# usbB_isp_no_lm2940.net
KiCad netlist of a schematic drawn in EAGLE
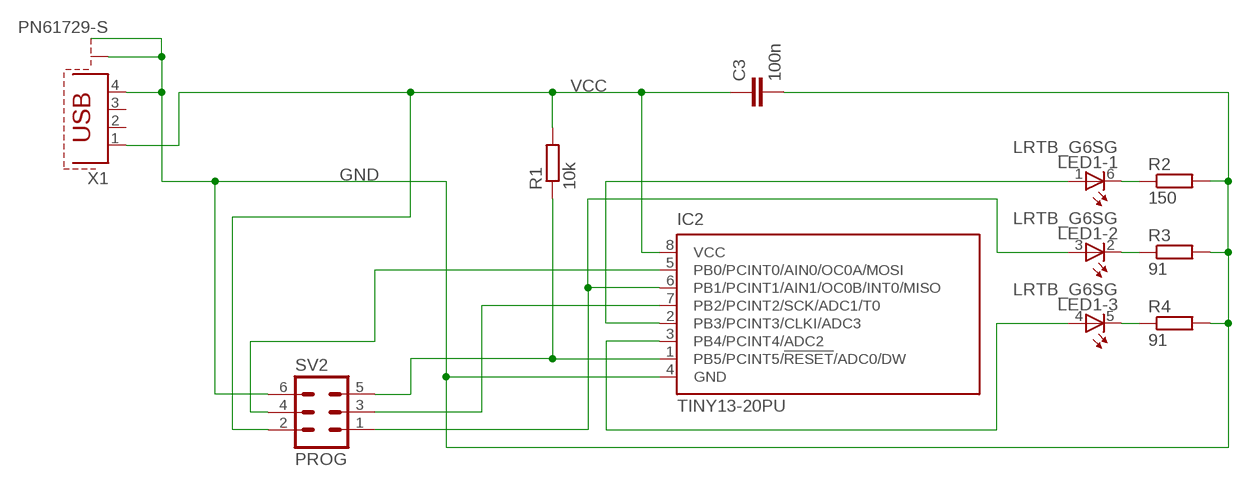
[diagram p0: schematic, sheet 1]

(export (version "E")
  (design (tool "Eeschema 10.0.6"))
  (components
    (comp (ref "C3")
      (value "100n")
      (footprint "eagle-import:C025-025X050")
      (libsource (lib "eagle-import") (part "C-EU025-025X050"))
    )
    (comp (ref "IC2")
      (value "TINY13-20PU")
      (footprint "eagle-import:DIL08")
      (fields (field (name "MPN") "ATTINY13-20PU"))
      (libsource (lib "eagle-import") (part "TINY13PU-20"))
    )
    (comp (ref "LED1")
      (value "LRTB_G6SG")
      (footprint "eagle-import:LRTB_G6SG")
      (libsource (lib "eagle-import") (part "LRTB_G6SG"))
    )
    (comp (ref "R1")
      (value "10k")
      (footprint "eagle-import:0207_10")
      (libsource (lib "eagle-import") (part "R-EU_0207/10"))
    )
    (comp (ref "R2")
      (value "150")
      (footprint "eagle-import:0207_10")
      (libsource (lib "eagle-import") (part "R-EU_0207/10"))
    )
    (comp (ref "R3")
      (value "91")
      (footprint "eagle-import:0207_10")
      (libsource (lib "eagle-import") (part "R-EU_0207/10"))
    )
    (comp (ref "R4")
      (value "91")
      (footprint "eagle-import:0207_10")
      (libsource (lib "eagle-import") (part "R-EU_0207/10"))
    )
    (comp (ref "SV2")
      (value "PROG")
      (footprint "eagle-import:ML6")
      (libsource (lib "eagle-import") (part "ML6"))
    )
    (comp (ref "X1")
      (value "PN61729-S")
      (footprint "eagle-import:PN61729-S")
      (libsource (lib "eagle-import") (part "PN61729-S"))
    )
  )
  (nets
    (net (code "1") (name "/GND") (class "Default")
      (node (ref "C3") (pin "2") (pinfunction "2_2") (pintype "passive"))
      (node (ref "IC2") (pin "4") (pinfunction "GND_4") (pintype "power_in"))
      (node (ref "R2") (pin "2") (pinfunction "2_2") (pintype "passive"))
      (node (ref "R3") (pin "2") (pinfunction "2_2") (pintype "passive"))
      (node (ref "R4") (pin "2") (pinfunction "2_2") (pintype "passive"))
      (node (ref "SV2") (pin "6") (pinfunction "6_6") (pintype "passive"))
      (node (ref "X1") (pin "4") (pinfunction "4_4") (pintype "passive"))
      (node (ref "X1") (pin "S1") (pinfunction "S1_S1") (pintype "passive"))
    )
    (net (code "2") (name "/VCC") (class "Default")
      (node (ref "C3") (pin "1") (pinfunction "1_1") (pintype "passive"))
      (node (ref "IC2") (pin "8") (pinfunction "VCC_8") (pintype "power_in"))
      (node (ref "R1") (pin "2") (pinfunction "2_2") (pintype "passive"))
      (node (ref "SV2") (pin "2") (pinfunction "2_2") (pintype "passive"))
      (node (ref "X1") (pin "1") (pinfunction "1_1") (pintype "passive"))
    )
    (net (code "3") (name "Net-(IC2-PB0{slash}PCINT0{slash}AIN0{slash}OC0A{slash}MOSI)") (class "Default")
      (node (ref "IC2") (pin "5") (pinfunction "PB0/PCINT0/AIN0/OC0A/MOSI_5") (pintype "bidirectional"))
      (node (ref "SV2") (pin "4") (pinfunction "4_4") (pintype "passive"))
    )
    (net (code "4") (name "Net-(IC2-PB1{slash}PCINT1{slash}AIN1{slash}OC0B{slash}INT0{slash}MISO)") (class "Default")
      (node (ref "IC2") (pin "6") (pinfunction "PB1/PCINT1/AIN1/OC0B/INT0/MISO_6") (pintype "bidirectional"))
      (node (ref "LED1") (pin "3") (pinfunction "A_3") (pintype "passive"))
      (node (ref "SV2") (pin "1") (pinfunction "1_1") (pintype "passive"))
    )
    (net (code "5") (name "Net-(IC2-PB2{slash}PCINT2{slash}SCK{slash}ADC1{slash}T0)") (class "Default")
      (node (ref "IC2") (pin "7") (pinfunction "PB2/PCINT2/SCK/ADC1/T0_7") (pintype "bidirectional"))
      (node (ref "SV2") (pin "3") (pinfunction "3_3") (pintype "passive"))
    )
    (net (code "6") (name "Net-(IC2-PB3{slash}PCINT3{slash}CLKI{slash}ADC3)") (class "Default")
      (node (ref "IC2") (pin "2") (pinfunction "PB3/PCINT3/CLKI/ADC3_2") (pintype "bidirectional"))
      (node (ref "LED1") (pin "1") (pinfunction "A_1") (pintype "passive"))
    )
    (net (code "7") (name "Net-(IC2-PB4{slash}PCINT4{slash}ADC2)") (class "Default")
      (node (ref "IC2") (pin "3") (pinfunction "PB4/PCINT4/ADC2_3") (pintype "bidirectional"))
      (node (ref "LED1") (pin "4") (pinfunction "A_4") (pintype "passive"))
    )
    (net (code "8") (name "Net-(IC2-PB5{slash}PCINT5{slash}~{RESET}{slash}ADC0{slash}DW)") (class "Default")
      (node (ref "IC2") (pin "1") (pinfunction "PB5/PCINT5/~{RESET}/ADC0/DW_1") (pintype "bidirectional"))
      (node (ref "R1") (pin "1") (pinfunction "1_1") (pintype "passive"))
      (node (ref "SV2") (pin "5") (pinfunction "5_5") (pintype "passive"))
    )
    (net (code "9") (name "Net-(LED1A-C)") (class "Default")
      (node (ref "LED1") (pin "6") (pinfunction "C_6") (pintype "passive"))
      (node (ref "R2") (pin "1") (pinfunction "1_1") (pintype "passive"))
    )
    (net (code "10") (name "Net-(LED1B-C)") (class "Default")
      (node (ref "LED1") (pin "2") (pinfunction "C_2") (pintype "passive"))
      (node (ref "R3") (pin "1") (pinfunction "1_1") (pintype "passive"))
    )
    (net (code "11") (name "Net-(LED1C-C)") (class "Default")
      (node (ref "LED1") (pin "5") (pinfunction "C_5") (pintype "passive"))
      (node (ref "R4") (pin "1") (pinfunction "1_1") (pintype "passive"))
    )
    (net (code "12") (name "unconnected-(X1-Pad2)") (class "Default")
      (node (ref "X1") (pin "2") (pinfunction "2_2") (pintype "passive"))
    )
    (net (code "13") (name "unconnected-(X1-Pad3)") (class "Default")
      (node (ref "X1") (pin "3") (pinfunction "3_3") (pintype "passive"))
    )
    (net (code "14") (name "unconnected-(X1-PadS2)") (class "Default")
      (node (ref "X1") (pin "S2") (pinfunction "S2_S2") (pintype "passive"))
    )
  )
)
